# Pi1541_Switch.net
KiCad netlist of a schematic drawn in EAGLE
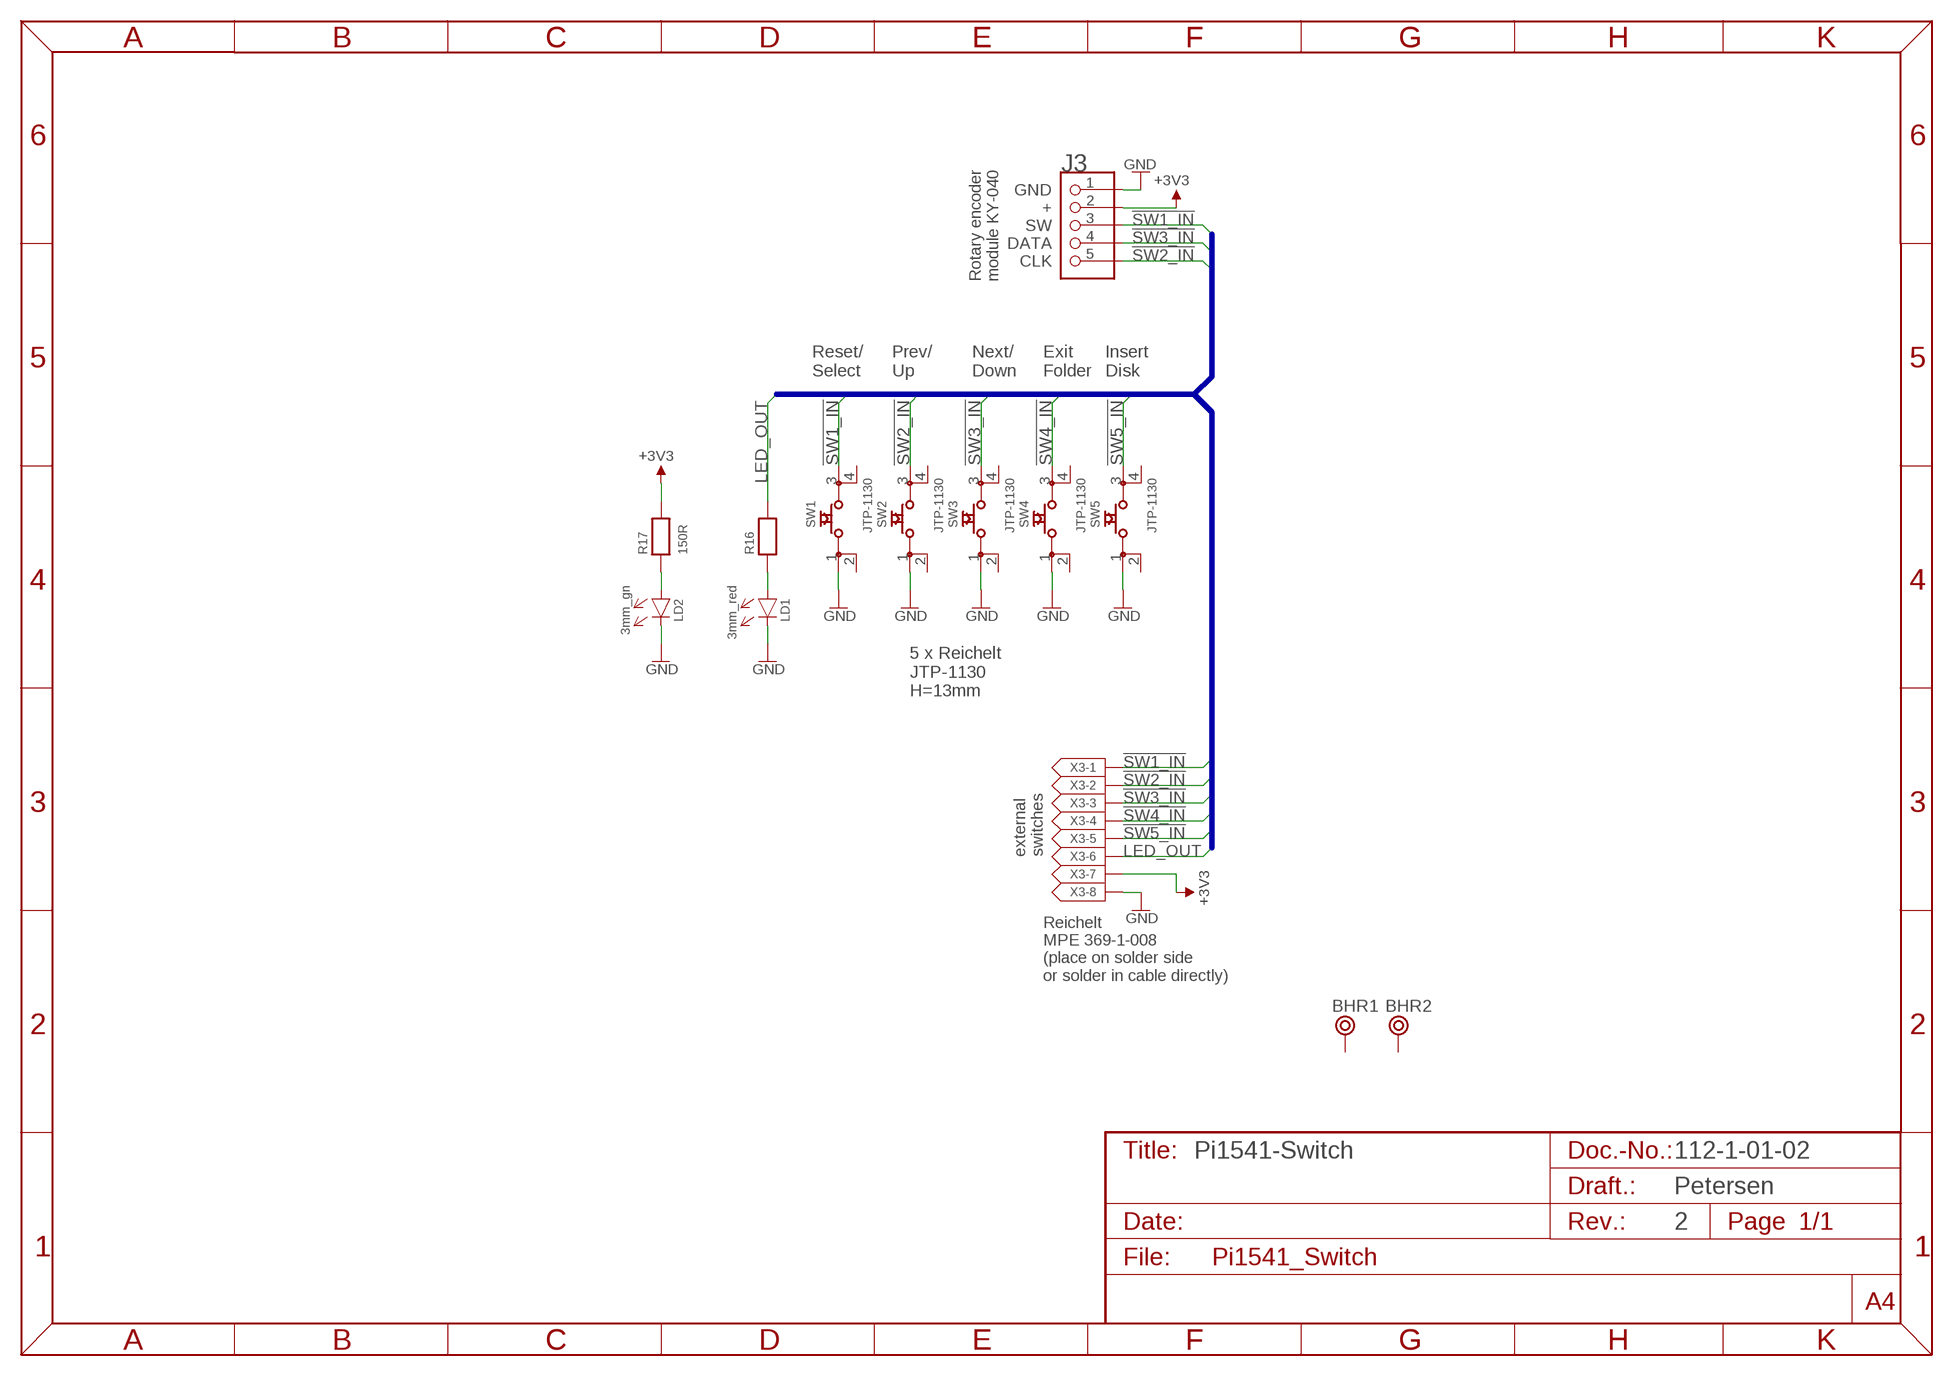
[diagram p0: schematic, sheet 1]

(export (version "E")
  (design (tool "Eeschema 10.0.6"))
  (components
    (comp (ref "BHR1")
      (value "BOHR2,8")
      (footprint "eagle-import:BOHR2,8_")
      (libsource (lib "eagle-import") (part "BOHR2,8"))
    )
    (comp (ref "BHR2")
      (value "BOHR2,8")
      (footprint "eagle-import:BOHR2,8_")
      (libsource (lib "eagle-import") (part "BOHR2,8"))
    )
    (comp (ref "J3")
      (value "PINHD-1X5")
      (footprint "eagle-import:1X05")
      (libsource (lib "eagle-import") (part "PINHD-1X5"))
    )
    (comp (ref "LD1")
      (value "3mm_red")
      (footprint "eagle-import:3MM")
      (libsource (lib "eagle-import") (part "3MM"))
    )
    (comp (ref "LD2")
      (value "3mm_gn")
      (footprint "eagle-import:3MM")
      (libsource (lib "eagle-import") (part "3MM"))
    )
    (comp (ref "R16")
      (value "150R")
      (footprint "eagle-import:0805")
      (libsource (lib "eagle-import") (part "R-0805"))
    )
    (comp (ref "R17")
      (value "150R")
      (footprint "eagle-import:0805")
      (libsource (lib "eagle-import") (part "R-0805"))
    )
    (comp (ref "SW1")
      (value "JTP-1130")
      (footprint "eagle-import:JTP-1130")
      (libsource (lib "eagle-import") (part "JTP-1130"))
    )
    (comp (ref "SW2")
      (value "JTP-1130")
      (footprint "eagle-import:JTP-1130")
      (libsource (lib "eagle-import") (part "JTP-1130"))
    )
    (comp (ref "SW3")
      (value "JTP-1130")
      (footprint "eagle-import:JTP-1130")
      (libsource (lib "eagle-import") (part "JTP-1130"))
    )
    (comp (ref "SW4")
      (value "JTP-1130")
      (footprint "eagle-import:JTP-1130")
      (libsource (lib "eagle-import") (part "JTP-1130"))
    )
    (comp (ref "SW5")
      (value "JTP-1130")
      (footprint "eagle-import:JTP-1130")
      (libsource (lib "eagle-import") (part "JTP-1130"))
    )
    (comp (ref "X3")
      (value "MICMA08B")
      (footprint "eagle-import:MICMA08B")
      (libsource (lib "eagle-import") (part "MICMA08B"))
    )
  )
  (nets
    (net (code "1") (name "+3V3") (class "Default")
      (node (ref "J3") (pin "2") (pinfunction "2_2") (pintype "passive"))
      (node (ref "R17") (pin "2") (pinfunction "2_2") (pintype "passive"))
      (node (ref "X3") (pin "7") (pinfunction "1_7") (pintype "bidirectional"))
    )
    (net (code "2") (name "/LED_OUT") (class "Default")
      (node (ref "R16") (pin "2") (pinfunction "2_2") (pintype "passive"))
      (node (ref "X3") (pin "6") (pinfunction "1_6") (pintype "bidirectional"))
    )
    (net (code "3") (name "/~{SW1_IN}") (class "Default")
      (node (ref "J3") (pin "3") (pinfunction "3_3") (pintype "passive"))
      (node (ref "SW1") (pin "3") (pinfunction "3_3") (pintype "passive"))
      (node (ref "X3") (pin "1") (pinfunction "1_1") (pintype "bidirectional"))
    )
    (net (code "4") (name "/~{SW2_IN}") (class "Default")
      (node (ref "J3") (pin "5") (pinfunction "5_5") (pintype "passive"))
      (node (ref "SW2") (pin "3") (pinfunction "3_3") (pintype "passive"))
      (node (ref "X3") (pin "2") (pinfunction "1_2") (pintype "bidirectional"))
    )
    (net (code "5") (name "/~{SW3_IN}") (class "Default")
      (node (ref "J3") (pin "4") (pinfunction "4_4") (pintype "passive"))
      (node (ref "SW3") (pin "3") (pinfunction "3_3") (pintype "passive"))
      (node (ref "X3") (pin "3") (pinfunction "1_3") (pintype "bidirectional"))
    )
    (net (code "6") (name "/~{SW4_IN}") (class "Default")
      (node (ref "SW4") (pin "3") (pinfunction "3_3") (pintype "passive"))
      (node (ref "X3") (pin "4") (pinfunction "1_4") (pintype "bidirectional"))
    )
    (net (code "7") (name "/~{SW5_IN}") (class "Default")
      (node (ref "SW5") (pin "3") (pinfunction "3_3") (pintype "passive"))
      (node (ref "X3") (pin "5") (pinfunction "1_5") (pintype "bidirectional"))
    )
    (net (code "8") (name "GND") (class "Default")
      (node (ref "J3") (pin "1") (pinfunction "1_1") (pintype "passive"))
      (node (ref "LD1") (pin "C") (pinfunction "K_C") (pintype "bidirectional"))
      (node (ref "LD2") (pin "C") (pinfunction "K_C") (pintype "bidirectional"))
      (node (ref "SW1") (pin "1") (pinfunction "1_1") (pintype "passive"))
      (node (ref "SW2") (pin "1") (pinfunction "1_1") (pintype "passive"))
      (node (ref "SW3") (pin "1") (pinfunction "1_1") (pintype "passive"))
      (node (ref "SW4") (pin "1") (pinfunction "1_1") (pintype "passive"))
      (node (ref "SW5") (pin "1") (pinfunction "1_1") (pintype "passive"))
      (node (ref "X3") (pin "8") (pinfunction "1_8") (pintype "bidirectional"))
    )
    (net (code "9") (name "Net-(LD1-PadA)") (class "Default")
      (node (ref "LD1") (pin "A") (pinfunction "A_A") (pintype "bidirectional"))
      (node (ref "R16") (pin "1") (pinfunction "1_1") (pintype "passive"))
    )
    (net (code "10") (name "Net-(LD2-PadA)") (class "Default")
      (node (ref "LD2") (pin "A") (pinfunction "A_A") (pintype "bidirectional"))
      (node (ref "R17") (pin "1") (pinfunction "1_1") (pintype "passive"))
    )
    (net (code "11") (name "unconnected-(BHR1-P$1-PadMH)") (class "Default")
      (node (ref "BHR1") (pin "MH") (pinfunction "P$1_MH") (pintype "passive"))
    )
    (net (code "12") (name "unconnected-(BHR2-P$1-PadMH)") (class "Default")
      (node (ref "BHR2") (pin "MH") (pinfunction "P$1_MH") (pintype "passive"))
    )
    (net (code "13") (name "unconnected-(SW1-Pad2)") (class "Default")
      (node (ref "SW1") (pin "2") (pinfunction "2_2") (pintype "passive"))
    )
    (net (code "14") (name "unconnected-(SW1-Pad4)") (class "Default")
      (node (ref "SW1") (pin "4") (pinfunction "4_4") (pintype "passive"))
    )
    (net (code "15") (name "unconnected-(SW2-Pad2)") (class "Default")
      (node (ref "SW2") (pin "2") (pinfunction "2_2") (pintype "passive"))
    )
    (net (code "16") (name "unconnected-(SW2-Pad4)") (class "Default")
      (node (ref "SW2") (pin "4") (pinfunction "4_4") (pintype "passive"))
    )
    (net (code "17") (name "unconnected-(SW3-Pad2)") (class "Default")
      (node (ref "SW3") (pin "2") (pinfunction "2_2") (pintype "passive"))
    )
    (net (code "18") (name "unconnected-(SW3-Pad4)") (class "Default")
      (node (ref "SW3") (pin "4") (pinfunction "4_4") (pintype "passive"))
    )
    (net (code "19") (name "unconnected-(SW4-Pad2)") (class "Default")
      (node (ref "SW4") (pin "2") (pinfunction "2_2") (pintype "passive"))
    )
    (net (code "20") (name "unconnected-(SW4-Pad4)") (class "Default")
      (node (ref "SW4") (pin "4") (pinfunction "4_4") (pintype "passive"))
    )
    (net (code "21") (name "unconnected-(SW5-Pad2)") (class "Default")
      (node (ref "SW5") (pin "2") (pinfunction "2_2") (pintype "passive"))
    )
    (net (code "22") (name "unconnected-(SW5-Pad4)") (class "Default")
      (node (ref "SW5") (pin "4") (pinfunction "4_4") (pintype "passive"))
    )
  )
)
